# Connector.net
KiCad netlist of a schematic drawn in Altium Designer
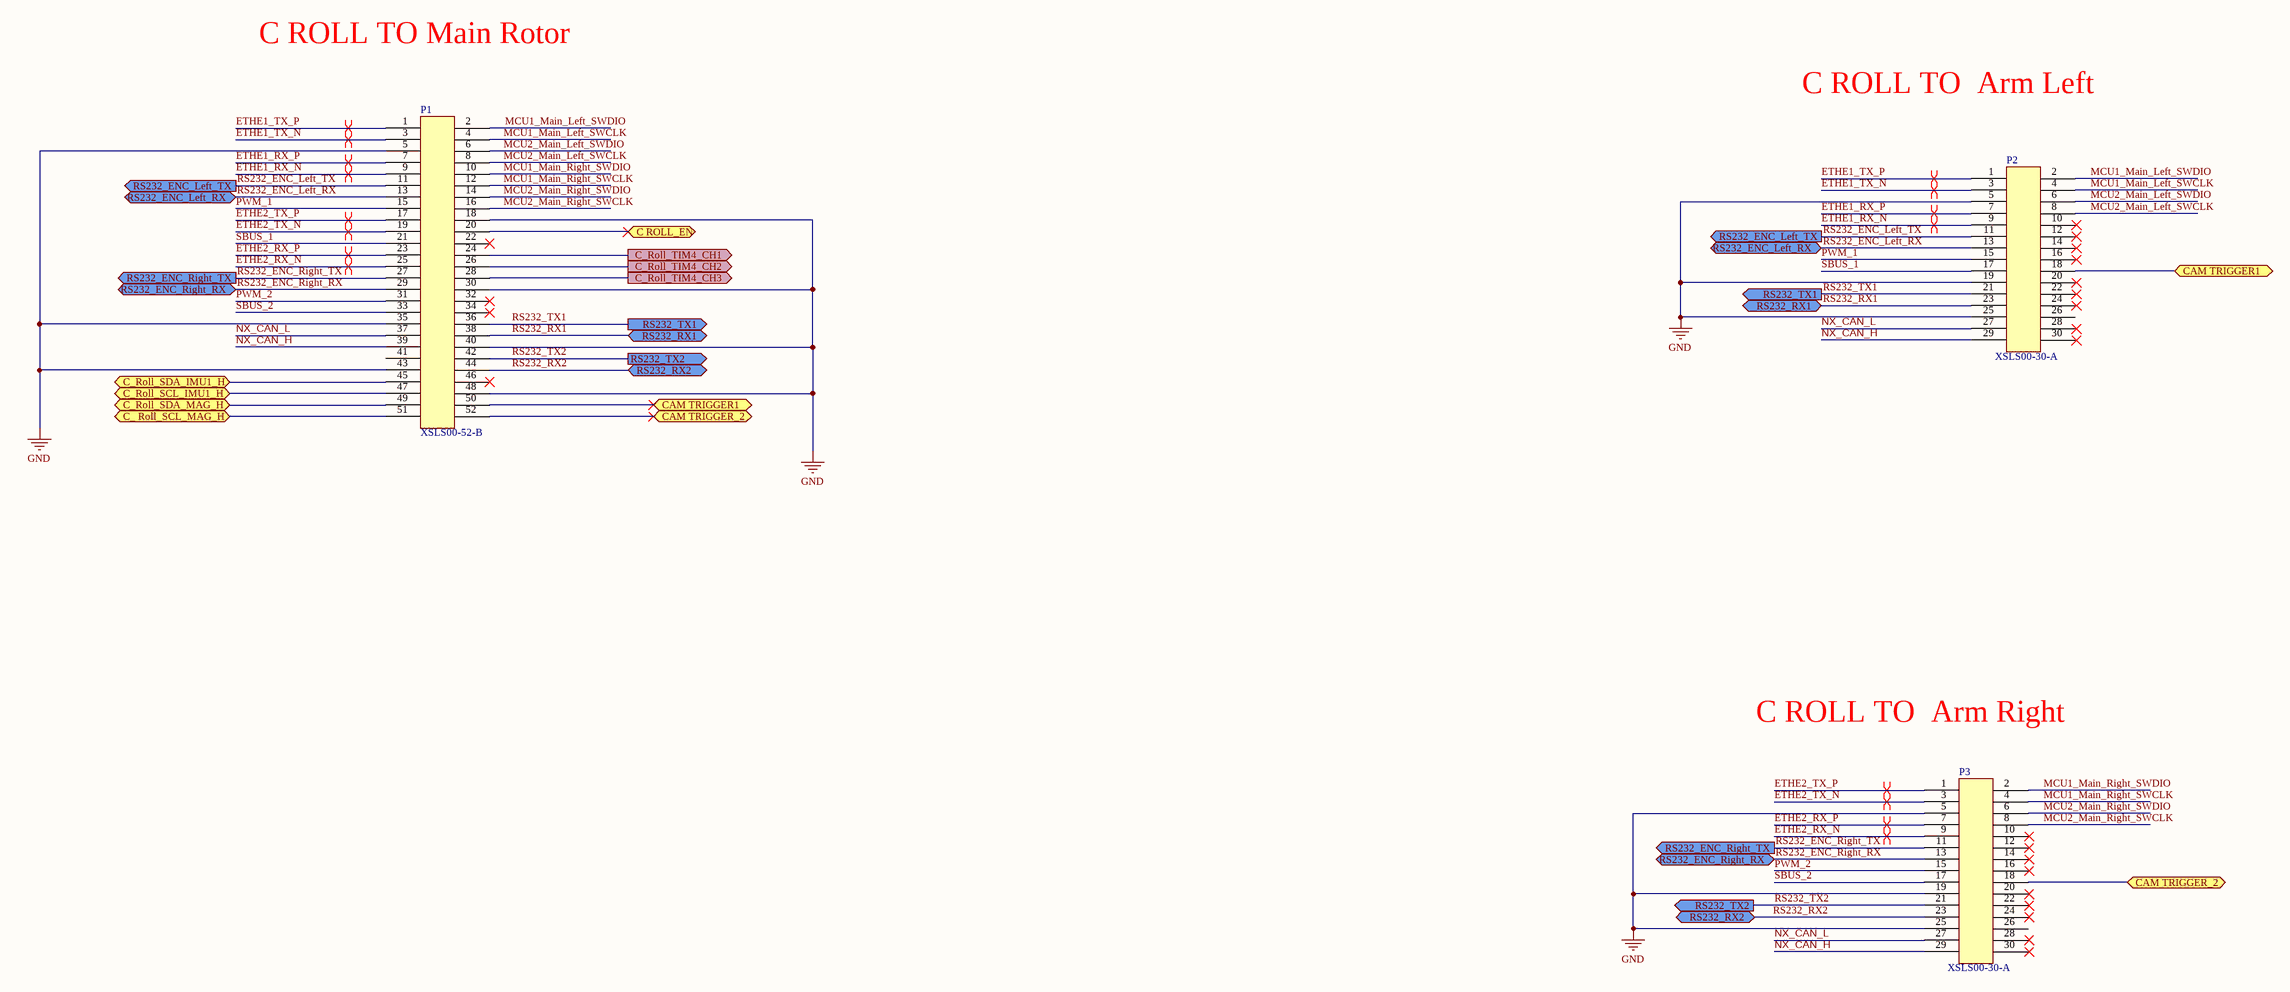
[diagram p0: Connector.SchDoc]

(export (version "E")
  (design (tool "Eeschema 10.0.6"))
  (components
    (comp (ref "P1")
      (value "XSLS00-52-B")
      (footprint "XSXL52")
      (libsource (lib "Hera_Sight_PixyU2") (part "XSLS00-52-B"))
    )
    (comp (ref "P2")
      (value "XSLS00-30-A")
      (footprint "XSXL30")
      (libsource (lib "XSLS00-30") (part "XSLS00-30-A"))
    )
    (comp (ref "P3")
      (value "XSLS00-30-A")
      (footprint "XSXL30")
      (libsource (lib "XSLS00-30") (part "XSLS00-30-A"))
    )
  )
  (nets
    (net (code "1") (name "/C ROLL_EN") (class "Default")
      (node (ref "P1") (pin "20") (pintype "passive+no_connect"))
    )
    (net (code "2") (name "/CAM TRIGGER1") (class "Default")
      (node (ref "P1") (pin "50") (pintype "passive"))
      (node (ref "P2") (pin "18") (pintype "passive"))
    )
    (net (code "3") (name "/CAM TRIGGER_2") (class "Default")
      (node (ref "P1") (pin "52") (pintype "passive"))
      (node (ref "P3") (pin "18") (pintype "passive"))
    )
    (net (code "4") (name "/C_ Roll_SCL_MAG_H") (class "Default")
      (node (ref "P1") (pin "51") (pintype "passive"))
    )
    (net (code "5") (name "/C_Roll_SCL_IMU1_H") (class "Default")
      (node (ref "P1") (pin "47") (pintype "passive"))
    )
    (net (code "6") (name "/C_Roll_SDA_IMU1_H") (class "Default")
      (node (ref "P1") (pin "45") (pintype "passive"))
    )
    (net (code "7") (name "/C_Roll_SDA_MAG_H") (class "Default")
      (node (ref "P1") (pin "49") (pintype "passive"))
    )
    (net (code "8") (name "/C_Roll_TIM4_CH1") (class "Default")
      (node (ref "P1") (pin "24") (pintype "passive"))
    )
    (net (code "9") (name "/C_Roll_TIM4_CH2") (class "Default")
      (node (ref "P1") (pin "26") (pintype "passive"))
    )
    (net (code "10") (name "/C_Roll_TIM4_CH3") (class "Default")
      (node (ref "P1") (pin "28") (pintype "passive"))
    )
    (net (code "11") (name "/ETHE1_RX_N") (class "Default")
      (node (ref "P1") (pin "9") (pintype "passive"))
      (node (ref "P2") (pin "9") (pintype "passive"))
    )
    (net (code "12") (name "/ETHE1_RX_P") (class "Default")
      (node (ref "P1") (pin "7") (pintype "passive"))
      (node (ref "P2") (pin "7") (pintype "passive"))
    )
    (net (code "13") (name "/ETHE1_TX_N") (class "Default")
      (node (ref "P1") (pin "3") (pintype "passive"))
      (node (ref "P2") (pin "3") (pintype "passive"))
    )
    (net (code "14") (name "/ETHE1_TX_P") (class "Default")
      (node (ref "P1") (pin "1") (pintype "passive"))
      (node (ref "P2") (pin "1") (pintype "passive"))
    )
    (net (code "15") (name "/ETHE2_RX_N") (class "Default")
      (node (ref "P1") (pin "25") (pintype "passive"))
      (node (ref "P3") (pin "9") (pintype "passive"))
    )
    (net (code "16") (name "/ETHE2_RX_P") (class "Default")
      (node (ref "P1") (pin "23") (pintype "passive"))
      (node (ref "P3") (pin "7") (pintype "passive"))
    )
    (net (code "17") (name "/ETHE2_TX_N") (class "Default")
      (node (ref "P1") (pin "19") (pintype "passive"))
      (node (ref "P3") (pin "3") (pintype "passive"))
    )
    (net (code "18") (name "/ETHE2_TX_P") (class "Default")
      (node (ref "P1") (pin "17") (pintype "passive"))
      (node (ref "P3") (pin "1") (pintype "passive"))
    )
    (net (code "19") (name "/MCU1_Main_Left_SWCLK") (class "Default")
      (node (ref "P1") (pin "4") (pintype "passive"))
      (node (ref "P2") (pin "4") (pintype "passive"))
    )
    (net (code "20") (name "/MCU1_Main_Left_SWDIO") (class "Default")
      (node (ref "P1") (pin "2") (pintype "passive"))
      (node (ref "P2") (pin "2") (pintype "passive"))
    )
    (net (code "21") (name "/MCU1_Main_Right_SWCLK") (class "Default")
      (node (ref "P1") (pin "12") (pintype "passive"))
      (node (ref "P3") (pin "4") (pintype "passive"))
    )
    (net (code "22") (name "/MCU1_Main_Right_SWDIO") (class "Default")
      (node (ref "P1") (pin "10") (pintype "passive"))
      (node (ref "P3") (pin "2") (pintype "passive"))
    )
    (net (code "23") (name "/MCU2_Main_Left_SWCLK") (class "Default")
      (node (ref "P1") (pin "8") (pintype "passive"))
      (node (ref "P2") (pin "8") (pintype "passive"))
    )
    (net (code "24") (name "/MCU2_Main_Left_SWDIO") (class "Default")
      (node (ref "P1") (pin "6") (pintype "passive"))
      (node (ref "P2") (pin "6") (pintype "passive"))
    )
    (net (code "25") (name "/MCU2_Main_Right_SWCLK") (class "Default")
      (node (ref "P1") (pin "16") (pintype "passive"))
      (node (ref "P3") (pin "8") (pintype "passive"))
    )
    (net (code "26") (name "/MCU2_Main_Right_SWDIO") (class "Default")
      (node (ref "P1") (pin "14") (pintype "passive"))
      (node (ref "P3") (pin "6") (pintype "passive"))
    )
    (net (code "27") (name "/NX_CAN_H") (class "Default")
      (node (ref "P1") (pin "39") (pintype "passive"))
      (node (ref "P2") (pin "29") (pintype "passive"))
      (node (ref "P3") (pin "29") (pintype "passive"))
    )
    (net (code "28") (name "/NX_CAN_L") (class "Default")
      (node (ref "P1") (pin "37") (pintype "passive"))
      (node (ref "P2") (pin "27") (pintype "passive"))
      (node (ref "P3") (pin "27") (pintype "passive"))
    )
    (net (code "29") (name "/PWM_1") (class "Default")
      (node (ref "P1") (pin "15") (pintype "passive"))
      (node (ref "P2") (pin "15") (pintype "passive"))
    )
    (net (code "30") (name "/PWM_2") (class "Default")
      (node (ref "P1") (pin "31") (pintype "passive"))
      (node (ref "P3") (pin "15") (pintype "passive"))
    )
    (net (code "31") (name "/RS232_ENC_Left_RX") (class "Default")
      (node (ref "P1") (pin "13") (pintype "passive"))
      (node (ref "P2") (pin "13") (pintype "passive"))
    )
    (net (code "32") (name "/RS232_ENC_Left_TX") (class "Default")
      (node (ref "P1") (pin "11") (pintype "passive"))
      (node (ref "P2") (pin "11") (pintype "passive"))
    )
    (net (code "33") (name "/RS232_ENC_Right_RX") (class "Default")
      (node (ref "P1") (pin "29") (pintype "passive"))
      (node (ref "P3") (pin "13") (pintype "passive"))
    )
    (net (code "34") (name "/RS232_ENC_Right_TX") (class "Default")
      (node (ref "P1") (pin "27") (pintype "passive"))
      (node (ref "P3") (pin "11") (pintype "passive"))
    )
    (net (code "35") (name "/RS232_RX1") (class "Default")
      (node (ref "P1") (pin "38") (pintype "passive"))
      (node (ref "P2") (pin "23") (pintype "passive"))
    )
    (net (code "36") (name "/RS232_RX2") (class "Default")
      (node (ref "P1") (pin "44") (pintype "passive"))
      (node (ref "P3") (pin "23") (pintype "passive"))
    )
    (net (code "37") (name "/RS232_TX1") (class "Default")
      (node (ref "P1") (pin "36") (pintype "passive"))
      (node (ref "P2") (pin "21") (pintype "passive"))
    )
    (net (code "38") (name "/RS232_TX2") (class "Default")
      (node (ref "P1") (pin "42") (pintype "passive"))
      (node (ref "P3") (pin "21") (pintype "passive"))
    )
    (net (code "39") (name "/SBUS_1") (class "Default")
      (node (ref "P1") (pin "21") (pintype "passive"))
      (node (ref "P2") (pin "17") (pintype "passive"))
    )
    (net (code "40") (name "/SBUS_2") (class "Default")
      (node (ref "P1") (pin "33") (pintype "passive"))
      (node (ref "P3") (pin "17") (pintype "passive"))
    )
    (net (code "41") (name "GND") (class "Default")
      (node (ref "P1") (pin "18") (pintype "passive"))
      (node (ref "P1") (pin "30") (pintype "passive"))
      (node (ref "P1") (pin "35") (pintype "passive"))
      (node (ref "P1") (pin "40") (pintype "passive"))
      (node (ref "P1") (pin "43") (pintype "passive"))
      (node (ref "P1") (pin "48") (pintype "passive"))
      (node (ref "P1") (pin "5") (pintype "passive"))
      (node (ref "P2") (pin "19") (pintype "passive"))
      (node (ref "P2") (pin "25") (pintype "passive"))
      (node (ref "P2") (pin "5") (pintype "passive"))
      (node (ref "P3") (pin "19") (pintype "passive"))
      (node (ref "P3") (pin "25") (pintype "passive"))
      (node (ref "P3") (pin "5") (pintype "passive"))
    )
    (net (code "42") (name "unconnected-(P1-Pad22)") (class "Default")
      (node (ref "P1") (pin "22") (pintype "passive+no_connect"))
    )
    (net (code "43") (name "unconnected-(P1-Pad32)") (class "Default")
      (node (ref "P1") (pin "32") (pintype "passive+no_connect"))
    )
    (net (code "44") (name "unconnected-(P1-Pad34)") (class "Default")
      (node (ref "P1") (pin "34") (pintype "passive+no_connect"))
    )
    (net (code "45") (name "unconnected-(P1-Pad41)") (class "Default")
      (node (ref "P1") (pin "41") (pintype "passive"))
    )
    (net (code "46") (name "unconnected-(P1-Pad46)") (class "Default")
      (node (ref "P1") (pin "46") (pintype "passive+no_connect"))
    )
    (net (code "47") (name "unconnected-(P2-Pad10)") (class "Default")
      (node (ref "P2") (pin "10") (pintype "passive"))
    )
    (net (code "48") (name "unconnected-(P2-Pad12)") (class "Default")
      (node (ref "P2") (pin "12") (pintype "passive"))
    )
    (net (code "49") (name "unconnected-(P2-Pad14)") (class "Default")
      (node (ref "P2") (pin "14") (pintype "passive"))
    )
    (net (code "50") (name "unconnected-(P2-Pad16)") (class "Default")
      (node (ref "P2") (pin "16") (pintype "passive"))
    )
    (net (code "51") (name "unconnected-(P2-Pad20)") (class "Default")
      (node (ref "P2") (pin "20") (pintype "passive"))
    )
    (net (code "52") (name "unconnected-(P2-Pad22)") (class "Default")
      (node (ref "P2") (pin "22") (pintype "passive"))
    )
    (net (code "53") (name "unconnected-(P2-Pad24)") (class "Default")
      (node (ref "P2") (pin "24") (pintype "passive"))
    )
    (net (code "54") (name "unconnected-(P2-Pad26)") (class "Default")
      (node (ref "P2") (pin "26") (pintype "passive"))
    )
    (net (code "55") (name "unconnected-(P2-Pad28)") (class "Default")
      (node (ref "P2") (pin "28") (pintype "passive"))
    )
    (net (code "56") (name "unconnected-(P2-Pad30)") (class "Default")
      (node (ref "P2") (pin "30") (pintype "passive"))
    )
    (net (code "57") (name "unconnected-(P3-Pad10)") (class "Default")
      (node (ref "P3") (pin "10") (pintype "passive"))
    )
    (net (code "58") (name "unconnected-(P3-Pad12)") (class "Default")
      (node (ref "P3") (pin "12") (pintype "passive"))
    )
    (net (code "59") (name "unconnected-(P3-Pad14)") (class "Default")
      (node (ref "P3") (pin "14") (pintype "passive"))
    )
    (net (code "60") (name "unconnected-(P3-Pad16)") (class "Default")
      (node (ref "P3") (pin "16") (pintype "passive"))
    )
    (net (code "61") (name "unconnected-(P3-Pad20)") (class "Default")
      (node (ref "P3") (pin "20") (pintype "passive"))
    )
    (net (code "62") (name "unconnected-(P3-Pad22)") (class "Default")
      (node (ref "P3") (pin "22") (pintype "passive"))
    )
    (net (code "63") (name "unconnected-(P3-Pad24)") (class "Default")
      (node (ref "P3") (pin "24") (pintype "passive"))
    )
    (net (code "64") (name "unconnected-(P3-Pad26)") (class "Default")
      (node (ref "P3") (pin "26") (pintype "passive"))
    )
    (net (code "65") (name "unconnected-(P3-Pad28)") (class "Default")
      (node (ref "P3") (pin "28") (pintype "passive"))
    )
    (net (code "66") (name "unconnected-(P3-Pad30)") (class "Default")
      (node (ref "P3") (pin "30") (pintype "passive"))
    )
  )
)
